# livia-90-semi-auto-board.net
KiCad netlist of a schematic drawn in EAGLE
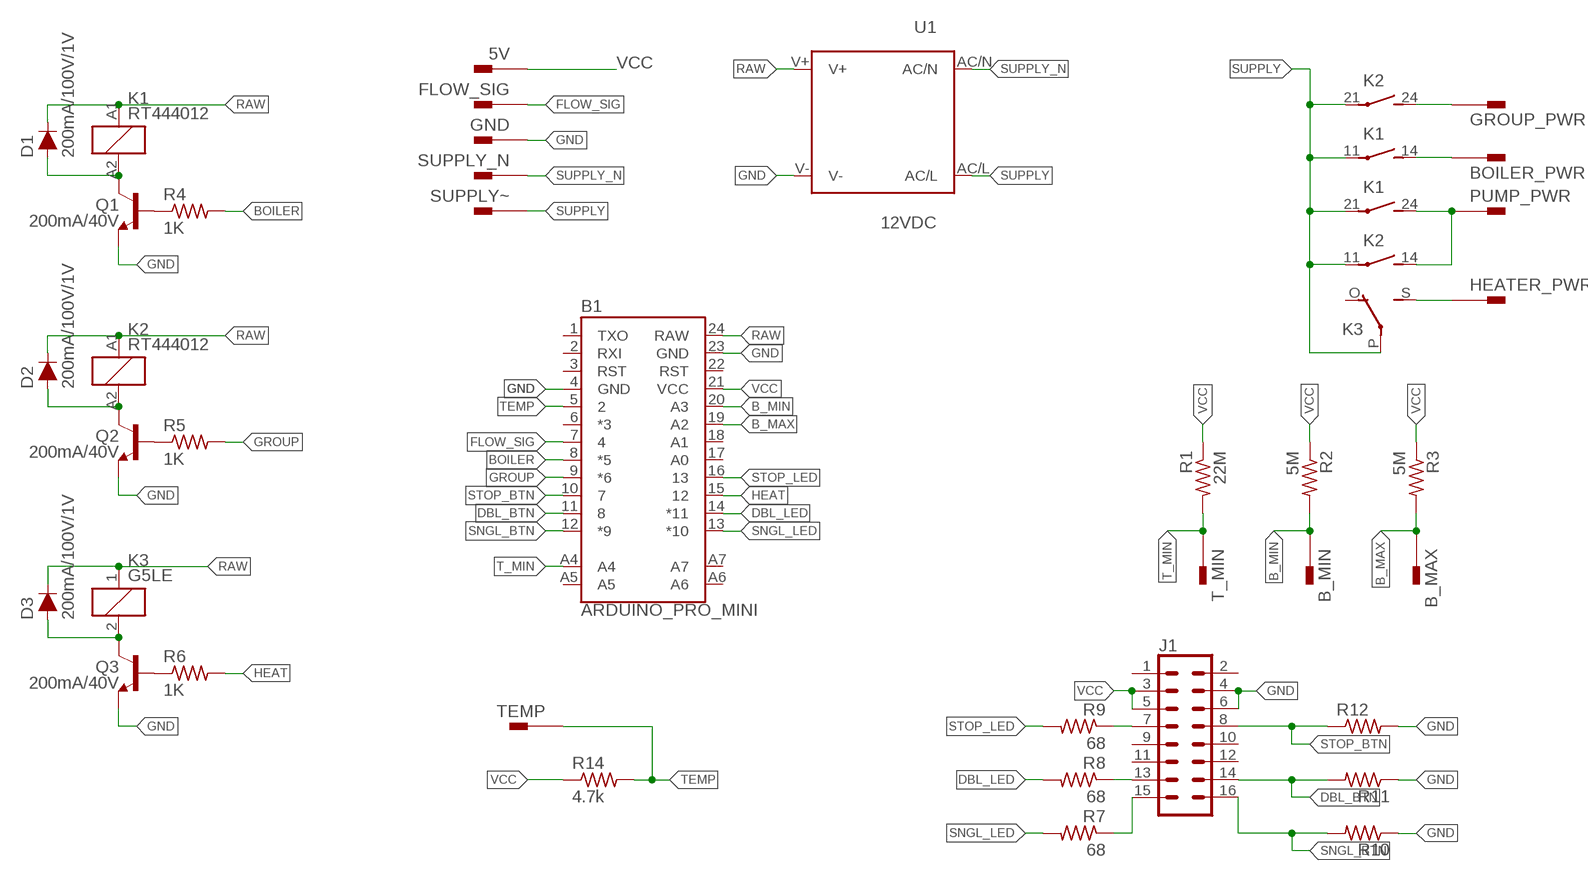
[diagram p0: schematic, sheet 1]

(export (version "E")
  (design (tool "Eeschema 10.0.6"))
  (components
    (comp (ref "5V")
      (value "PIN2F061.040")
      (footprint "eagle-import:F061.040")
      (libsource (lib "eagle-import") (part "PIN2F061.040"))
    )
    (comp (ref "B1")
      (value "ARDUINO_PRO_MINI")
      (footprint "eagle-import:ARDUINO_PRO_MINI")
      (libsource (lib "eagle-import") (part "ARDUINO_PRO_MINI"))
    )
    (comp (ref "BOILER_PWR")
      (value "PIN2F061.040")
      (footprint "eagle-import:F061.040")
      (libsource (lib "eagle-import") (part "PIN2F061.040"))
    )
    (comp (ref "B_MAX")
      (value "PIN2F061.040")
      (footprint "eagle-import:F061.040")
      (libsource (lib "eagle-import") (part "PIN2F061.040"))
    )
    (comp (ref "B_MIN")
      (value "PIN2F061.040")
      (footprint "eagle-import:F061.040")
      (libsource (lib "eagle-import") (part "PIN2F061.040"))
    )
    (comp (ref "D1")
      (value "200mA/100V/1V")
      (footprint "eagle-import:DIODE-1N4148")
      (libsource (lib "eagle-import") (part "DIODE-1N4148"))
    )
    (comp (ref "D2")
      (value "200mA/100V/1V")
      (footprint "eagle-import:DIODE-1N4148")
      (libsource (lib "eagle-import") (part "DIODE-1N4148"))
    )
    (comp (ref "D3")
      (value "200mA/100V/1V")
      (footprint "eagle-import:DIODE-1N4148")
      (libsource (lib "eagle-import") (part "DIODE-1N4148"))
    )
    (comp (ref "FLOW_SIG")
      (value "PIN2F061.040")
      (footprint "eagle-import:F061.040")
      (libsource (lib "eagle-import") (part "PIN2F061.040"))
    )
    (comp (ref "GND")
      (value "PIN2F061.040")
      (footprint "eagle-import:F061.040")
      (libsource (lib "eagle-import") (part "PIN2F061.040"))
    )
    (comp (ref "GROUP_PWR")
      (value "PIN2F061.040")
      (footprint "eagle-import:F061.040")
      (libsource (lib "eagle-import") (part "PIN2F061.040"))
    )
    (comp (ref "HEATER_PWR")
      (value "PIN2F061.040")
      (footprint "eagle-import:F061.040")
      (libsource (lib "eagle-import") (part "PIN2F061.040"))
    )
    (comp (ref "J1")
      (value "CONN_08X2")
      (footprint "eagle-import:2X8")
      (libsource (lib "eagle-import") (part "CONN_08X2"))
    )
    (comp (ref "K1")
      (value "RT444012")
      (footprint "eagle-import:RT2N_O")
      (libsource (lib "eagle-import") (part "RT44?4012"))
    )
    (comp (ref "K2")
      (value "RT444012")
      (footprint "eagle-import:RT2N_O")
      (libsource (lib "eagle-import") (part "RT44?4012"))
    )
    (comp (ref "K3")
      (value "G5LE")
      (footprint "eagle-import:G5LE")
      (libsource (lib "eagle-import") (part "G5LE"))
    )
    (comp (ref "PUMP_PWR")
      (value "PIN2F061.040")
      (footprint "eagle-import:F061.040")
      (libsource (lib "eagle-import") (part "PIN2F061.040"))
    )
    (comp (ref "Q1")
      (value "200mA/40V")
      (footprint "eagle-import:TO-92")
      (libsource (lib "eagle-import") (part "TRANS_NPN-2N3904"))
    )
    (comp (ref "Q2")
      (value "200mA/40V")
      (footprint "eagle-import:TO-92")
      (libsource (lib "eagle-import") (part "TRANS_NPN-2N3904"))
    )
    (comp (ref "Q3")
      (value "200mA/40V")
      (footprint "eagle-import:TO-92")
      (libsource (lib "eagle-import") (part "TRANS_NPN-2N3904"))
    )
    (comp (ref "R1")
      (value "22M")
      (footprint "eagle-import:0207_7")
      (libsource (lib "eagle-import") (part "R-US_0207/7"))
    )
    (comp (ref "R2")
      (value "5M")
      (footprint "eagle-import:0207_7")
      (libsource (lib "eagle-import") (part "R-US_0207/7"))
    )
    (comp (ref "R3")
      (value "5M")
      (footprint "eagle-import:0207_7")
      (libsource (lib "eagle-import") (part "R-US_0207/7"))
    )
    (comp (ref "R4")
      (value "1K")
      (footprint "eagle-import:0207_7")
      (libsource (lib "eagle-import") (part "R-US_0207/7"))
    )
    (comp (ref "R5")
      (value "1K")
      (footprint "eagle-import:0207_7")
      (libsource (lib "eagle-import") (part "R-US_0207/7"))
    )
    (comp (ref "R6")
      (value "1K")
      (footprint "eagle-import:0207_7")
      (libsource (lib "eagle-import") (part "R-US_0207/7"))
    )
    (comp (ref "R7")
      (value "68")
      (footprint "eagle-import:0207_7")
      (libsource (lib "eagle-import") (part "R-US_0207/7"))
    )
    (comp (ref "R8")
      (value "68")
      (footprint "eagle-import:0207_7")
      (libsource (lib "eagle-import") (part "R-US_0207/7"))
    )
    (comp (ref "R9")
      (value "68")
      (footprint "eagle-import:0207_7")
      (libsource (lib "eagle-import") (part "R-US_0207/7"))
    )
    (comp (ref "R10")
      (value "R-US_0207/7")
      (footprint "eagle-import:0207_7")
      (libsource (lib "eagle-import") (part "R-US_0207/7"))
    )
    (comp (ref "R11")
      (value "R-US_0207/7")
      (footprint "eagle-import:0207_7")
      (libsource (lib "eagle-import") (part "R-US_0207/7"))
    )
    (comp (ref "R12")
      (value "R-US_0207/7")
      (footprint "eagle-import:0207_7")
      (libsource (lib "eagle-import") (part "R-US_0207/7"))
    )
    (comp (ref "R14")
      (value "4.7k")
      (footprint "eagle-import:0207_7")
      (libsource (lib "eagle-import") (part "R-US_0207/7"))
    )
    (comp (ref "SUPPLY_N")
      (value "PIN2F061.040")
      (footprint "eagle-import:F061.040")
      (libsource (lib "eagle-import") (part "PIN2F061.040"))
    )
    (comp (ref "SUPPLY~")
      (value "PIN2F061.040")
      (footprint "eagle-import:F061.040")
      (libsource (lib "eagle-import") (part "PIN2F061.040"))
    )
    (comp (ref "TEMP")
      (value "PIN2F061.040")
      (footprint "eagle-import:F061.040")
      (libsource (lib "eagle-import") (part "PIN2F061.040"))
    )
    (comp (ref "T_MIN")
      (value "PIN2F061.040")
      (footprint "eagle-import:F061.040")
      (libsource (lib "eagle-import") (part "PIN2F061.040"))
    )
    (comp (ref "U1")
      (value "12VDC")
      (footprint "eagle-import:IRM_05_10")
      (libsource (lib "eagle-import") (part "IRM_05/10"))
    )
  )
  (nets
    (net (code "1") (name "BOILER") (class "Default")
      (node (ref "B1") (pin "8") (pinfunction "*5_8") (pintype "bidirectional"))
      (node (ref "R4") (pin "2") (pinfunction "2_2") (pintype "passive"))
    )
    (net (code "2") (name "B_MAX") (class "Default")
      (node (ref "B1") (pin "19") (pinfunction "A2_19") (pintype "bidirectional"))
      (node (ref "B_MAX") (pin "A1") (pinfunction "1_A1") (pintype "passive"))
      (node (ref "B_MAX") (pin "A2") (pinfunction "1_A2") (pintype "passive"))
      (node (ref "R3") (pin "2") (pinfunction "2_2") (pintype "passive"))
    )
    (net (code "3") (name "B_MIN") (class "Default")
      (node (ref "B1") (pin "20") (pinfunction "A3_20") (pintype "bidirectional"))
      (node (ref "B_MIN") (pin "A1") (pinfunction "1_A1") (pintype "passive"))
      (node (ref "B_MIN") (pin "A2") (pinfunction "1_A2") (pintype "passive"))
      (node (ref "R2") (pin "2") (pinfunction "2_2") (pintype "passive"))
    )
    (net (code "4") (name "DBL_BTN") (class "Default")
      (node (ref "B1") (pin "11") (pinfunction "8_11") (pintype "bidirectional"))
      (node (ref "J1") (pin "14") (pinfunction "14_14") (pintype "passive"))
      (node (ref "R11") (pin "2") (pinfunction "2_2") (pintype "passive"))
    )
    (net (code "5") (name "DBL_LED") (class "Default")
      (node (ref "B1") (pin "14") (pinfunction "*11_14") (pintype "bidirectional"))
      (node (ref "R8") (pin "2") (pinfunction "2_2") (pintype "passive"))
    )
    (net (code "6") (name "FLOW_SIG") (class "Default")
      (node (ref "B1") (pin "7") (pinfunction "4_7") (pintype "bidirectional"))
      (node (ref "FLOW_SIG") (pin "A1") (pinfunction "1_A1") (pintype "passive"))
      (node (ref "FLOW_SIG") (pin "A2") (pinfunction "1_A2") (pintype "passive"))
    )
    (net (code "7") (name "GND") (class "Default")
      (node (ref "B1") (pin "23") (pinfunction "GND_23") (pintype "power_in"))
      (node (ref "B1") (pin "4") (pinfunction "GND_4") (pintype "power_in"))
      (node (ref "GND") (pin "A1") (pinfunction "1_A1") (pintype "passive"))
      (node (ref "GND") (pin "A2") (pinfunction "1_A2") (pintype "passive"))
      (node (ref "J1") (pin "4") (pinfunction "4_4") (pintype "passive"))
      (node (ref "J1") (pin "6") (pinfunction "6_6") (pintype "passive"))
      (node (ref "Q1") (pin "1") (pinfunction "E_1") (pintype "passive"))
      (node (ref "Q2") (pin "1") (pinfunction "E_1") (pintype "passive"))
      (node (ref "Q3") (pin "1") (pinfunction "E_1") (pintype "passive"))
      (node (ref "R10") (pin "1") (pinfunction "1_1") (pintype "passive"))
      (node (ref "R11") (pin "1") (pinfunction "1_1") (pintype "passive"))
      (node (ref "R12") (pin "2") (pinfunction "2_2") (pintype "passive"))
      (node (ref "U1") (pin "V-") (pinfunction "V-_V-") (pintype "output"))
    )
    (net (code "8") (name "GROUP") (class "Default")
      (node (ref "B1") (pin "9") (pinfunction "*6_9") (pintype "bidirectional"))
      (node (ref "R5") (pin "2") (pinfunction "2_2") (pintype "passive"))
    )
    (net (code "9") (name "HEAT") (class "Default")
      (node (ref "B1") (pin "15") (pinfunction "12_15") (pintype "bidirectional"))
      (node (ref "R6") (pin "2") (pinfunction "2_2") (pintype "passive"))
    )
    (net (code "10") (name "Net-(HEATER_PWR-1-PadA1)") (class "Default")
      (node (ref "HEATER_PWR") (pin "A1") (pinfunction "1_A1") (pintype "passive"))
      (node (ref "HEATER_PWR") (pin "A2") (pinfunction "1_A2") (pintype "passive"))
      (node (ref "K3") (pin "S") (pinfunction "S_S") (pintype "passive"))
    )
    (net (code "11") (name "Net-(J1-Pad7)") (class "Default")
      (node (ref "J1") (pin "7") (pinfunction "7_7") (pintype "passive"))
      (node (ref "R9") (pin "1") (pinfunction "1_1") (pintype "passive"))
    )
    (net (code "12") (name "Net-(J1-Pad13)") (class "Default")
      (node (ref "J1") (pin "13") (pinfunction "13_13") (pintype "passive"))
      (node (ref "R8") (pin "1") (pinfunction "1_1") (pintype "passive"))
    )
    (net (code "13") (name "Net-(J1-Pad15)") (class "Default")
      (node (ref "J1") (pin "15") (pinfunction "15_15") (pintype "passive"))
      (node (ref "R7") (pin "1") (pinfunction "1_1") (pintype "passive"))
    )
    (net (code "14") (name "Net-(K1A-2)") (class "Default")
      (node (ref "D1") (pin "A") (pinfunction "A_A") (pintype "passive"))
      (node (ref "K1") (pin "A2") (pinfunction "2_A2") (pintype "passive"))
      (node (ref "Q1") (pin "3") (pinfunction "C_3") (pintype "passive"))
    )
    (net (code "15") (name "Net-(K1B-S)") (class "Default")
      (node (ref "BOILER_PWR") (pin "A1") (pinfunction "1_A1") (pintype "passive"))
      (node (ref "BOILER_PWR") (pin "A2") (pinfunction "1_A2") (pintype "passive"))
      (node (ref "K1") (pin "14") (pinfunction "S_14") (pintype "passive"))
    )
    (net (code "16") (name "Net-(K1C-S)") (class "Default")
      (node (ref "K1") (pin "24") (pinfunction "S_24") (pintype "passive"))
      (node (ref "K2") (pin "14") (pinfunction "S_14") (pintype "passive"))
      (node (ref "PUMP_PWR") (pin "A1") (pinfunction "1_A1") (pintype "passive"))
      (node (ref "PUMP_PWR") (pin "A2") (pinfunction "1_A2") (pintype "passive"))
    )
    (net (code "17") (name "Net-(K2A-2)") (class "Default")
      (node (ref "D2") (pin "A") (pinfunction "A_A") (pintype "passive"))
      (node (ref "K2") (pin "A2") (pinfunction "2_A2") (pintype "passive"))
      (node (ref "Q2") (pin "3") (pinfunction "C_3") (pintype "passive"))
    )
    (net (code "18") (name "Net-(K2C-S)") (class "Default")
      (node (ref "GROUP_PWR") (pin "A1") (pinfunction "1_A1") (pintype "passive"))
      (node (ref "GROUP_PWR") (pin "A2") (pinfunction "1_A2") (pintype "passive"))
      (node (ref "K2") (pin "24") (pinfunction "S_24") (pintype "passive"))
    )
    (net (code "19") (name "Net-(Q1-B)") (class "Default")
      (node (ref "Q1") (pin "2") (pinfunction "B_2") (pintype "passive"))
      (node (ref "R4") (pin "1") (pinfunction "1_1") (pintype "passive"))
    )
    (net (code "20") (name "Net-(Q2-B)") (class "Default")
      (node (ref "Q2") (pin "2") (pinfunction "B_2") (pintype "passive"))
      (node (ref "R5") (pin "1") (pinfunction "1_1") (pintype "passive"))
    )
    (net (code "21") (name "Net-(Q3-B)") (class "Default")
      (node (ref "Q3") (pin "2") (pinfunction "B_2") (pintype "passive"))
      (node (ref "R6") (pin "1") (pinfunction "1_1") (pintype "passive"))
    )
    (net (code "22") (name "Net-(Q3-C)") (class "Default")
      (node (ref "D3") (pin "A") (pinfunction "A_A") (pintype "passive"))
      (node (ref "K3") (pin "2") (pinfunction "2_2") (pintype "passive"))
      (node (ref "Q3") (pin "3") (pinfunction "C_3") (pintype "passive"))
    )
    (net (code "23") (name "RAW") (class "Default")
      (node (ref "B1") (pin "24") (pinfunction "RAW_24") (pintype "power_in"))
      (node (ref "D1") (pin "C") (pinfunction "C_C") (pintype "passive"))
      (node (ref "D2") (pin "C") (pinfunction "C_C") (pintype "passive"))
      (node (ref "D3") (pin "C") (pinfunction "C_C") (pintype "passive"))
      (node (ref "K1") (pin "A1") (pinfunction "1_A1") (pintype "passive"))
      (node (ref "K2") (pin "A1") (pinfunction "1_A1") (pintype "passive"))
      (node (ref "K3") (pin "1") (pinfunction "1_1") (pintype "passive"))
      (node (ref "U1") (pin "V+") (pinfunction "V+_V+") (pintype "output"))
    )
    (net (code "24") (name "SNGL_BTN") (class "Default")
      (node (ref "B1") (pin "12") (pinfunction "*9_12") (pintype "bidirectional"))
      (node (ref "J1") (pin "16") (pinfunction "16_16") (pintype "passive"))
      (node (ref "R10") (pin "2") (pinfunction "2_2") (pintype "passive"))
    )
    (net (code "25") (name "SNGL_LED") (class "Default")
      (node (ref "B1") (pin "13") (pinfunction "*10_13") (pintype "bidirectional"))
      (node (ref "R7") (pin "2") (pinfunction "2_2") (pintype "passive"))
    )
    (net (code "26") (name "STOP_BTN") (class "Default")
      (node (ref "B1") (pin "10") (pinfunction "7_10") (pintype "bidirectional"))
      (node (ref "J1") (pin "8") (pinfunction "8_8") (pintype "passive"))
      (node (ref "R12") (pin "1") (pinfunction "1_1") (pintype "passive"))
    )
    (net (code "27") (name "STOP_LED") (class "Default")
      (node (ref "B1") (pin "16") (pinfunction "13_16") (pintype "bidirectional"))
      (node (ref "R9") (pin "2") (pinfunction "2_2") (pintype "passive"))
    )
    (net (code "28") (name "SUPPLY") (class "Default")
      (node (ref "K1") (pin "11") (pinfunction "P_11") (pintype "passive"))
      (node (ref "K1") (pin "21") (pinfunction "P_21") (pintype "passive"))
      (node (ref "K2") (pin "11") (pinfunction "P_11") (pintype "passive"))
      (node (ref "K2") (pin "21") (pinfunction "P_21") (pintype "passive"))
      (node (ref "K3") (pin "P") (pinfunction "P_P") (pintype "passive"))
      (node (ref "SUPPLY~") (pin "A1") (pinfunction "1_A1") (pintype "passive"))
      (node (ref "SUPPLY~") (pin "A2") (pinfunction "1_A2") (pintype "passive"))
      (node (ref "U1") (pin "AC/L") (pinfunction "AC/L_AC/L") (pintype "input"))
    )
    (net (code "29") (name "SUPPLY_N") (class "Default")
      (node (ref "SUPPLY_N") (pin "A1") (pinfunction "1_A1") (pintype "passive"))
      (node (ref "SUPPLY_N") (pin "A2") (pinfunction "1_A2") (pintype "passive"))
      (node (ref "U1") (pin "AC/N") (pinfunction "AC/N_AC/N") (pintype "input"))
    )
    (net (code "30") (name "TEMP") (class "Default")
      (node (ref "B1") (pin "5") (pinfunction "2_5") (pintype "bidirectional"))
      (node (ref "R14") (pin "2") (pinfunction "2_2") (pintype "passive"))
      (node (ref "TEMP") (pin "A1") (pinfunction "1_A1") (pintype "passive"))
      (node (ref "TEMP") (pin "A2") (pinfunction "1_A2") (pintype "passive"))
    )
    (net (code "31") (name "T_MIN") (class "Default")
      (node (ref "B1") (pin "A4") (pinfunction "A4_A4") (pintype "bidirectional"))
      (node (ref "R1") (pin "2") (pinfunction "2_2") (pintype "passive"))
      (node (ref "T_MIN") (pin "A1") (pinfunction "1_A1") (pintype "passive"))
      (node (ref "T_MIN") (pin "A2") (pinfunction "1_A2") (pintype "passive"))
    )
    (net (code "32") (name "VCC") (class "Default")
      (node (ref "5V") (pin "A1") (pinfunction "1_A1") (pintype "passive"))
      (node (ref "5V") (pin "A2") (pinfunction "1_A2") (pintype "passive"))
      (node (ref "B1") (pin "21") (pinfunction "VCC_21") (pintype "power_in"))
      (node (ref "J1") (pin "3") (pinfunction "3_3") (pintype "passive"))
      (node (ref "J1") (pin "5") (pinfunction "5_5") (pintype "passive"))
      (node (ref "R1") (pin "1") (pinfunction "1_1") (pintype "passive"))
      (node (ref "R14") (pin "1") (pinfunction "1_1") (pintype "passive"))
      (node (ref "R2") (pin "1") (pinfunction "1_1") (pintype "passive"))
      (node (ref "R3") (pin "1") (pinfunction "1_1") (pintype "passive"))
    )
    (net (code "33") (name "unconnected-(B1-*3-Pad6)") (class "Default")
      (node (ref "B1") (pin "6") (pinfunction "*3_6") (pintype "bidirectional"))
    )
    (net (code "34") (name "unconnected-(B1-A0-Pad17)") (class "Default")
      (node (ref "B1") (pin "17") (pinfunction "A0_17") (pintype "bidirectional"))
    )
    (net (code "35") (name "unconnected-(B1-A1-Pad18)") (class "Default")
      (node (ref "B1") (pin "18") (pinfunction "A1_18") (pintype "bidirectional"))
    )
    (net (code "36") (name "unconnected-(B1-PadA5)") (class "Default")
      (node (ref "B1") (pin "A5") (pinfunction "A5_A5") (pintype "bidirectional"))
    )
    (net (code "37") (name "unconnected-(B1-PadA6)") (class "Default")
      (node (ref "B1") (pin "A6") (pinfunction "A6_A6") (pintype "bidirectional"))
    )
    (net (code "38") (name "unconnected-(B1-PadA7)") (class "Default")
      (node (ref "B1") (pin "A7") (pinfunction "A7_A7") (pintype "bidirectional"))
    )
    (net (code "39") (name "unconnected-(B1-RST-Pad3)") (class "Default")
      (node (ref "B1") (pin "3") (pinfunction "RST_3") (pintype "bidirectional"))
    )
    (net (code "40") (name "unconnected-(B1-RST-Pad22)") (class "Default")
      (node (ref "B1") (pin "22") (pinfunction "RST_22") (pintype "bidirectional"))
    )
    (net (code "41") (name "unconnected-(B1-RXI-Pad2)") (class "Default")
      (node (ref "B1") (pin "2") (pinfunction "RXI_2") (pintype "bidirectional"))
    )
    (net (code "42") (name "unconnected-(B1-TXO-Pad1)") (class "Default")
      (node (ref "B1") (pin "1") (pinfunction "TXO_1") (pintype "bidirectional"))
    )
    (net (code "43") (name "unconnected-(J1-Pad1)") (class "Default")
      (node (ref "J1") (pin "1") (pinfunction "1_1") (pintype "passive"))
    )
    (net (code "44") (name "unconnected-(J1-Pad2)") (class "Default")
      (node (ref "J1") (pin "2") (pinfunction "2_2") (pintype "passive"))
    )
    (net (code "45") (name "unconnected-(J1-Pad9)") (class "Default")
      (node (ref "J1") (pin "9") (pinfunction "9_9") (pintype "passive"))
    )
    (net (code "46") (name "unconnected-(J1-Pad10)") (class "Default")
      (node (ref "J1") (pin "10") (pinfunction "10_10") (pintype "passive"))
    )
    (net (code "47") (name "unconnected-(J1-Pad11)") (class "Default")
      (node (ref "J1") (pin "11") (pinfunction "11_11") (pintype "passive"))
    )
    (net (code "48") (name "unconnected-(J1-Pad12)") (class "Default")
      (node (ref "J1") (pin "12") (pinfunction "12_12") (pintype "passive"))
    )
    (net (code "49") (name "unconnected-(K3-PadO)") (class "Default")
      (node (ref "K3") (pin "O") (pinfunction "O_O") (pintype "passive"))
    )
  )
)
